# test2.net
KiCad netlist of a schematic drawn in EAGLE
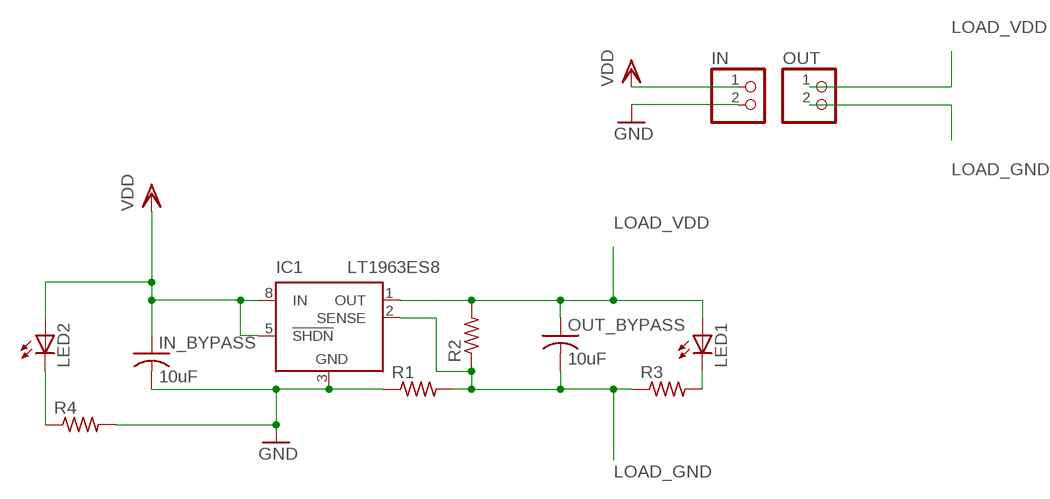
[diagram p0: schematic, sheet 1]

(export (version "E")
  (design (tool "Eeschema 10.0.6"))
  (components
    (comp (ref "IC1")
      (value "LT1963ES8")
      (footprint "eagle-import:SOIC8")
      (libsource (lib "eagle-import") (part "LT1963ES8"))
    )
    (comp (ref "IN")
      (value "PINHD-1X2")
      (footprint "eagle-import:1X02")
      (libsource (lib "eagle-import") (part "PINHD-1X2"))
    )
    (comp (ref "IN_BYPASS")
      (value "10uF")
      (footprint "eagle-import:C1206")
      (libsource (lib "eagle-import") (part "C-USC1206"))
    )
    (comp (ref "LED1")
      (value "LEDCHIPLED_1206")
      (footprint "eagle-import:CHIPLED_1206")
      (libsource (lib "eagle-import") (part "LEDCHIPLED_1206"))
    )
    (comp (ref "LED2")
      (value "LEDCHIPLED_1206")
      (footprint "eagle-import:CHIPLED_1206")
      (libsource (lib "eagle-import") (part "LEDCHIPLED_1206"))
    )
    (comp (ref "OUT")
      (value "PINHD-1X2")
      (footprint "eagle-import:1X02")
      (libsource (lib "eagle-import") (part "PINHD-1X2"))
    )
    (comp (ref "OUT_BYPASS")
      (value "10uF")
      (footprint "eagle-import:C1206")
      (libsource (lib "eagle-import") (part "C-USC1206"))
    )
    (comp (ref "R1")
      (value "R-US_R1206")
      (footprint "eagle-import:R1206")
      (libsource (lib "eagle-import") (part "R-US_R1206"))
    )
    (comp (ref "R2")
      (value "R-US_R1206")
      (footprint "eagle-import:R1206")
      (libsource (lib "eagle-import") (part "R-US_R1206"))
    )
    (comp (ref "R3")
      (value "R-US_R1206")
      (footprint "eagle-import:R1206")
      (libsource (lib "eagle-import") (part "R-US_R1206"))
    )
    (comp (ref "R4")
      (value "R-US_R1206")
      (footprint "eagle-import:R1206")
      (libsource (lib "eagle-import") (part "R-US_R1206"))
    )
  )
  (nets
    (net (code "1") (name "/LOAD_GND") (class "Default")
      (node (ref "IC1") (pin "2") (pinfunction "SENSE_2") (pintype "input"))
      (node (ref "OUT") (pin "2") (pinfunction "2_2") (pintype "passive"))
      (node (ref "OUT_BYPASS") (pin "2") (pinfunction "2_2") (pintype "passive"))
      (node (ref "R1") (pin "2") (pinfunction "2_2") (pintype "passive"))
      (node (ref "R2") (pin "1") (pinfunction "1_1") (pintype "passive"))
      (node (ref "R3") (pin "1") (pinfunction "1_1") (pintype "passive"))
    )
    (net (code "2") (name "/LOAD_VDD") (class "Default")
      (node (ref "IC1") (pin "1") (pinfunction "OUT_1") (pintype "output"))
      (node (ref "LED1") (pin "A") (pinfunction "A_A") (pintype "passive"))
      (node (ref "OUT") (pin "1") (pinfunction "1_1") (pintype "passive"))
      (node (ref "OUT_BYPASS") (pin "1") (pinfunction "1_1") (pintype "passive"))
      (node (ref "R2") (pin "2") (pinfunction "2_2") (pintype "passive"))
    )
    (net (code "3") (name "GND") (class "Default")
      (node (ref "IC1") (pin "3") (pinfunction "GND_3") (pintype "power_in"))
      (node (ref "IN") (pin "2") (pinfunction "2_2") (pintype "passive"))
      (node (ref "IN_BYPASS") (pin "2") (pinfunction "2_2") (pintype "passive"))
      (node (ref "R1") (pin "1") (pinfunction "1_1") (pintype "passive"))
      (node (ref "R4") (pin "2") (pinfunction "2_2") (pintype "passive"))
    )
    (net (code "4") (name "Net-(LED1-PadC)") (class "Default")
      (node (ref "LED1") (pin "C") (pinfunction "C_C") (pintype "passive"))
      (node (ref "R3") (pin "2") (pinfunction "2_2") (pintype "passive"))
    )
    (net (code "5") (name "Net-(LED2-PadC)") (class "Default")
      (node (ref "LED2") (pin "C") (pinfunction "C_C") (pintype "passive"))
      (node (ref "R4") (pin "1") (pinfunction "1_1") (pintype "passive"))
    )
    (net (code "6") (name "VDD") (class "Default")
      (node (ref "IC1") (pin "5") (pinfunction "~{SHDN}_5") (pintype "input"))
      (node (ref "IC1") (pin "8") (pinfunction "IN_8") (pintype "input"))
      (node (ref "IN") (pin "1") (pinfunction "1_1") (pintype "passive"))
      (node (ref "IN_BYPASS") (pin "1") (pinfunction "1_1") (pintype "passive"))
      (node (ref "LED2") (pin "A") (pinfunction "A_A") (pintype "passive"))
    )
  )
)
